# AVR_Board_4_0_FTDI_Ports.net
KiCad netlist of a schematic drawn in Altium Designer
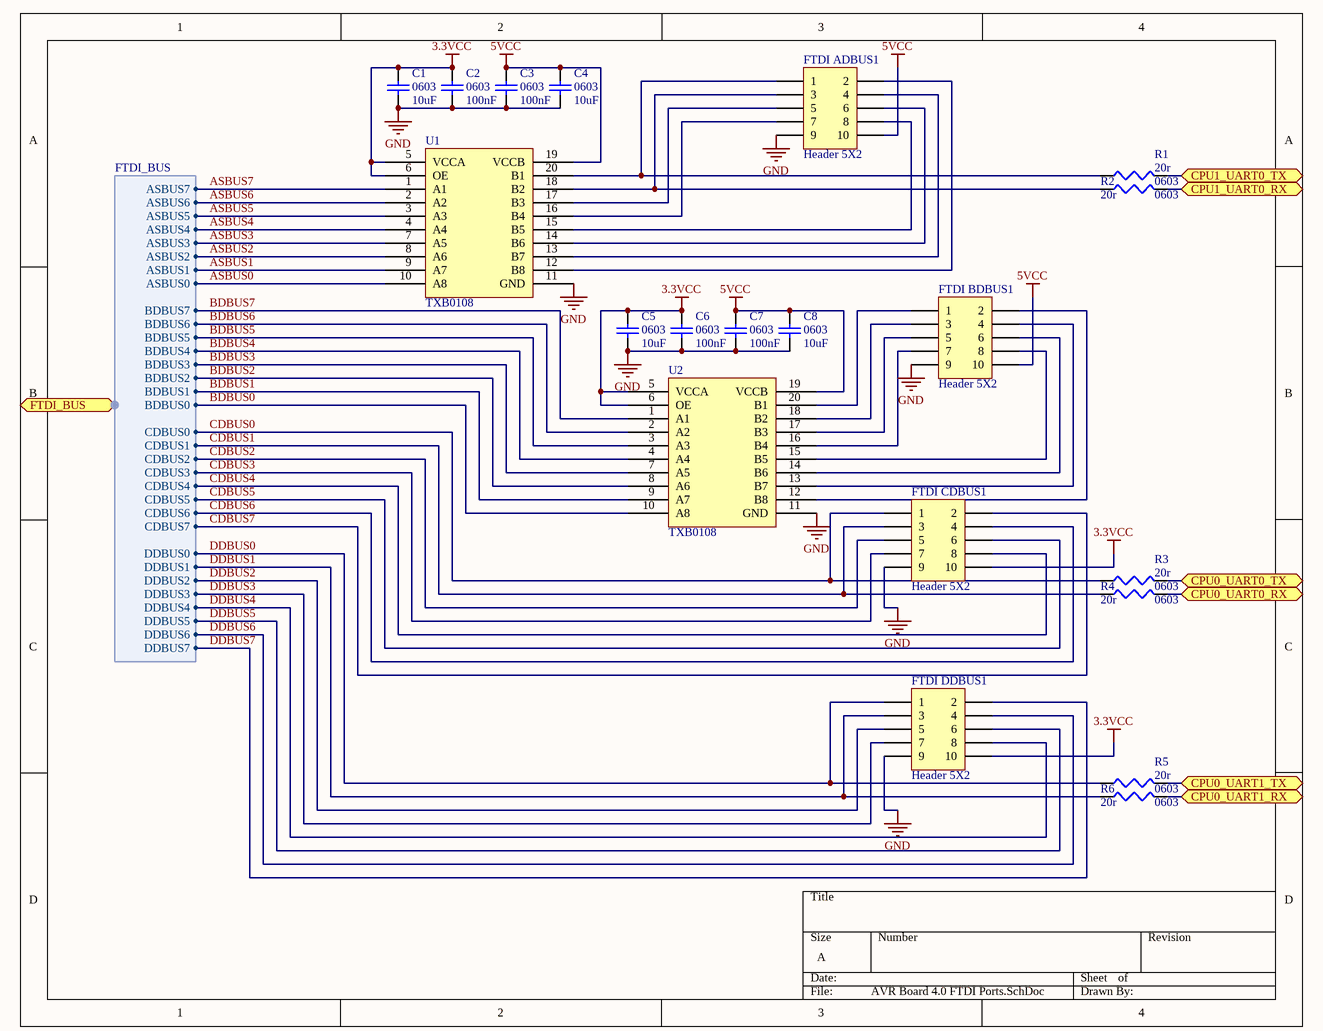
[diagram p0: AVR Board 4.0 FTDI Ports.SchDoc]

(export (version "E")
  (design (tool "Eeschema 10.0.6"))
  (components
    (comp (ref "C1")
      (value "0603")
      (footprint "1608[0603]")
      (description "Capacitor (Semiconductor SIM Model)")
      (fields (field (name "ALTIUM_VALUE") "10uF") (field (name "PUBLISHER") "Altium Limited"))
      (libsource (lib "Miscellaneous Devices") (part "Cap Semi"))
    )
    (comp (ref "C2")
      (value "0603")
      (footprint "1608[0603]")
      (description "Capacitor (Semiconductor SIM Model)")
      (fields (field (name "ALTIUM_VALUE") "100nF") (field (name "PUBLISHER") "Altium Limited"))
      (libsource (lib "Miscellaneous Devices") (part "Cap Semi"))
    )
    (comp (ref "C3")
      (value "0603")
      (footprint "1608[0603]")
      (description "Capacitor (Semiconductor SIM Model)")
      (fields (field (name "ALTIUM_VALUE") "100nF") (field (name "PUBLISHER") "Altium Limited"))
      (libsource (lib "Miscellaneous Devices") (part "Cap Semi"))
    )
    (comp (ref "C4")
      (value "0603")
      (footprint "1608[0603]")
      (description "Capacitor (Semiconductor SIM Model)")
      (fields (field (name "ALTIUM_VALUE") "10uF") (field (name "PUBLISHER") "Altium Limited"))
      (libsource (lib "Miscellaneous Devices") (part "Cap Semi"))
    )
    (comp (ref "C5")
      (value "0603")
      (footprint "1608[0603]")
      (description "Capacitor (Semiconductor SIM Model)")
      (fields (field (name "ALTIUM_VALUE") "10uF") (field (name "PUBLISHER") "Altium Limited"))
      (libsource (lib "Miscellaneous Devices") (part "Cap Semi"))
    )
    (comp (ref "C6")
      (value "0603")
      (footprint "1608[0603]")
      (description "Capacitor (Semiconductor SIM Model)")
      (fields (field (name "ALTIUM_VALUE") "100nF") (field (name "PUBLISHER") "Altium Limited"))
      (libsource (lib "Miscellaneous Devices") (part "Cap Semi"))
    )
    (comp (ref "C7")
      (value "0603")
      (footprint "1608[0603]")
      (description "Capacitor (Semiconductor SIM Model)")
      (fields (field (name "ALTIUM_VALUE") "100nF") (field (name "PUBLISHER") "Altium Limited"))
      (libsource (lib "Miscellaneous Devices") (part "Cap Semi"))
    )
    (comp (ref "C8")
      (value "0603")
      (footprint "1608[0603]")
      (description "Capacitor (Semiconductor SIM Model)")
      (fields (field (name "ALTIUM_VALUE") "10uF") (field (name "PUBLISHER") "Altium Limited"))
      (libsource (lib "Miscellaneous Devices") (part "Cap Semi"))
    )
    (comp (ref "FTDI ADBUS1")
      (value "Header 5X2")
      (footprint "HDR2X5")
      (description "Header, 5-Pin, Dual row")
      (fields (field (name "PUBLISHER") "Altium Limited"))
      (libsource (lib "Miscellaneous Connectors") (part "Header 5X2"))
    )
    (comp (ref "FTDI BDBUS1")
      (value "Header 5X2")
      (footprint "HDR2X5")
      (description "Header, 5-Pin, Dual row")
      (fields (field (name "PUBLISHER") "Altium Limited"))
      (libsource (lib "Miscellaneous Connectors") (part "Header 5X2"))
    )
    (comp (ref "FTDI CDBUS1")
      (value "Header 5X2")
      (footprint "HDR2X5")
      (description "Header, 5-Pin, Dual row")
      (fields (field (name "PUBLISHER") "Altium Limited"))
      (libsource (lib "Miscellaneous Connectors") (part "Header 5X2"))
    )
    (comp (ref "FTDI DDBUS1")
      (value "Header 5X2")
      (footprint "HDR2X5")
      (description "Header, 5-Pin, Dual row")
      (fields (field (name "PUBLISHER") "Altium Limited"))
      (libsource (lib "Miscellaneous Connectors") (part "Header 5X2"))
    )
    (comp (ref "R1")
      (value "0603")
      (footprint "J1-0603")
      (description "Resistor")
      (fields (field (name "ALTIUM_VALUE") "20r") (field (name "PUBLISHER") "Altium Limited"))
      (libsource (lib "Miscellaneous Devices") (part "Res3"))
    )
    (comp (ref "R2")
      (value "0603")
      (footprint "J1-0603")
      (description "Resistor")
      (fields (field (name "ALTIUM_VALUE") "20r") (field (name "PUBLISHER") "Altium Limited"))
      (libsource (lib "Miscellaneous Devices") (part "Res3"))
    )
    (comp (ref "R3")
      (value "0603")
      (footprint "J1-0603")
      (description "Resistor")
      (fields (field (name "ALTIUM_VALUE") "20r") (field (name "PUBLISHER") "Altium Limited"))
      (libsource (lib "Miscellaneous Devices") (part "Res3"))
    )
    (comp (ref "R4")
      (value "0603")
      (footprint "J1-0603")
      (description "Resistor")
      (fields (field (name "ALTIUM_VALUE") "20r") (field (name "PUBLISHER") "Altium Limited"))
      (libsource (lib "Miscellaneous Devices") (part "Res3"))
    )
    (comp (ref "R5")
      (value "0603")
      (footprint "J1-0603")
      (description "Resistor")
      (fields (field (name "ALTIUM_VALUE") "20r") (field (name "PUBLISHER") "Altium Limited"))
      (libsource (lib "Miscellaneous Devices") (part "Res3"))
    )
    (comp (ref "R6")
      (value "0603")
      (footprint "J1-0603")
      (description "Resistor")
      (fields (field (name "ALTIUM_VALUE") "20r") (field (name "PUBLISHER") "Altium Limited"))
      (libsource (lib "Miscellaneous Devices") (part "Res3"))
    )
    (comp (ref "U1")
      (value "TXB0108")
      (footprint "TXB0108")
      (description "Ti TXB0108 Bidirectional Level Translator")
      (libsource (lib "AVR Board 4.0 Symbol Lib") (part "TXB0108"))
    )
    (comp (ref "U2")
      (value "TXB0108")
      (footprint "TXB0108")
      (description "Ti TXB0108 Bidirectional Level Translator")
      (libsource (lib "AVR Board 4.0 Symbol Lib") (part "TXB0108"))
    )
  )
  (nets
    (net (code "2") (name "/ASBUS0") (class "Default")
      (node (ref "U1") (pin "10") (pinfunction "A8_10") (pintype "passive"))
    )
    (net (code "3") (name "/ASBUS1") (class "Default")
      (node (ref "U1") (pin "9") (pinfunction "A7_9") (pintype "passive"))
    )
    (net (code "4") (name "/ASBUS2") (class "Default")
      (node (ref "U1") (pin "8") (pinfunction "A6_8") (pintype "passive"))
    )
    (net (code "5") (name "/ASBUS3") (class "Default")
      (node (ref "U1") (pin "7") (pinfunction "A5_7") (pintype "passive"))
    )
    (net (code "6") (name "/ASBUS4") (class "Default")
      (node (ref "U1") (pin "4") (pinfunction "A4_4") (pintype "passive"))
    )
    (net (code "7") (name "/ASBUS5") (class "Default")
      (node (ref "U1") (pin "3") (pinfunction "A3_3") (pintype "passive"))
    )
    (net (code "8") (name "/ASBUS6") (class "Default")
      (node (ref "U1") (pin "2") (pinfunction "A2_2") (pintype "passive"))
    )
    (net (code "9") (name "/ASBUS7") (class "Default")
      (node (ref "U1") (pin "1") (pinfunction "A1_1") (pintype "passive"))
    )
    (net (code "10") (name "/BDBUS0") (class "Default")
      (node (ref "U2") (pin "10") (pinfunction "A8_10") (pintype "passive"))
    )
    (net (code "11") (name "/BDBUS1") (class "Default")
      (node (ref "U2") (pin "9") (pinfunction "A7_9") (pintype "passive"))
    )
    (net (code "12") (name "/BDBUS2") (class "Default")
      (node (ref "U2") (pin "8") (pinfunction "A6_8") (pintype "passive"))
    )
    (net (code "13") (name "/BDBUS3") (class "Default")
      (node (ref "U2") (pin "7") (pinfunction "A5_7") (pintype "passive"))
    )
    (net (code "14") (name "/BDBUS4") (class "Default")
      (node (ref "U2") (pin "4") (pinfunction "A4_4") (pintype "passive"))
    )
    (net (code "15") (name "/BDBUS5") (class "Default")
      (node (ref "U2") (pin "3") (pinfunction "A3_3") (pintype "passive"))
    )
    (net (code "16") (name "/BDBUS6") (class "Default")
      (node (ref "U2") (pin "2") (pinfunction "A2_2") (pintype "passive"))
    )
    (net (code "17") (name "/BDBUS7") (class "Default")
      (node (ref "U2") (pin "1") (pinfunction "A1_1") (pintype "passive"))
    )
    (net (code "18") (name "/CDBUS0") (class "Default")
      (node (ref "FTDI CDBUS1") (pin "1") (pinfunction "1_1") (pintype "passive"))
      (node (ref "R3") (pin "1") (pinfunction "1_1") (pintype "passive"))
    )
    (net (code "19") (name "/CDBUS1") (class "Default")
      (node (ref "FTDI CDBUS1") (pin "3") (pinfunction "3_3") (pintype "passive"))
      (node (ref "R4") (pin "1") (pinfunction "1_1") (pintype "passive"))
    )
    (net (code "20") (name "/CDBUS2") (class "Default")
      (node (ref "FTDI CDBUS1") (pin "5") (pinfunction "5_5") (pintype "passive"))
    )
    (net (code "21") (name "/CDBUS3") (class "Default")
      (node (ref "FTDI CDBUS1") (pin "7") (pinfunction "7_7") (pintype "passive"))
    )
    (net (code "22") (name "/CDBUS4") (class "Default")
      (node (ref "FTDI CDBUS1") (pin "8") (pinfunction "8_8") (pintype "passive"))
    )
    (net (code "23") (name "/CDBUS5") (class "Default")
      (node (ref "FTDI CDBUS1") (pin "6") (pinfunction "6_6") (pintype "passive"))
    )
    (net (code "24") (name "/CDBUS6") (class "Default")
      (node (ref "FTDI CDBUS1") (pin "4") (pinfunction "4_4") (pintype "passive"))
    )
    (net (code "25") (name "/CDBUS7") (class "Default")
      (node (ref "FTDI CDBUS1") (pin "2") (pinfunction "2_2") (pintype "passive"))
    )
    (net (code "26") (name "/CPU0_UART0_RX") (class "Default")
      (node (ref "R4") (pin "2") (pinfunction "2_2") (pintype "passive"))
    )
    (net (code "27") (name "/CPU0_UART0_TX") (class "Default")
      (node (ref "R3") (pin "2") (pinfunction "2_2") (pintype "passive"))
    )
    (net (code "28") (name "/CPU0_UART1_RX") (class "Default")
      (node (ref "R6") (pin "2") (pinfunction "2_2") (pintype "passive"))
    )
    (net (code "29") (name "/CPU0_UART1_TX") (class "Default")
      (node (ref "R5") (pin "2") (pinfunction "2_2") (pintype "passive"))
    )
    (net (code "30") (name "/CPU1_UART0_RX") (class "Default")
      (node (ref "R2") (pin "2") (pinfunction "2_2") (pintype "passive"))
    )
    (net (code "31") (name "/CPU1_UART0_TX") (class "Default")
      (node (ref "R1") (pin "2") (pinfunction "2_2") (pintype "passive"))
    )
    (net (code "32") (name "/DDBUS0") (class "Default")
      (node (ref "FTDI DDBUS1") (pin "1") (pinfunction "1_1") (pintype "passive"))
      (node (ref "R5") (pin "1") (pinfunction "1_1") (pintype "passive"))
    )
    (net (code "33") (name "/DDBUS1") (class "Default")
      (node (ref "FTDI DDBUS1") (pin "3") (pinfunction "3_3") (pintype "passive"))
      (node (ref "R6") (pin "1") (pinfunction "1_1") (pintype "passive"))
    )
    (net (code "34") (name "/DDBUS2") (class "Default")
      (node (ref "FTDI DDBUS1") (pin "5") (pinfunction "5_5") (pintype "passive"))
    )
    (net (code "35") (name "/DDBUS3") (class "Default")
      (node (ref "FTDI DDBUS1") (pin "7") (pinfunction "7_7") (pintype "passive"))
    )
    (net (code "36") (name "/DDBUS4") (class "Default")
      (node (ref "FTDI DDBUS1") (pin "8") (pinfunction "8_8") (pintype "passive"))
    )
    (net (code "37") (name "/DDBUS5") (class "Default")
      (node (ref "FTDI DDBUS1") (pin "6") (pinfunction "6_6") (pintype "passive"))
    )
    (net (code "38") (name "/DDBUS6") (class "Default")
      (node (ref "FTDI DDBUS1") (pin "4") (pinfunction "4_4") (pintype "passive"))
    )
    (net (code "39") (name "/DDBUS7") (class "Default")
      (node (ref "FTDI DDBUS1") (pin "2") (pinfunction "2_2") (pintype "passive"))
    )
    (net (code "41") (name "3.3VCC") (class "Default")
      (node (ref "C1") (pin "2") (pinfunction "2_2") (pintype "passive"))
      (node (ref "C2") (pin "2") (pinfunction "2_2") (pintype "passive"))
      (node (ref "C5") (pin "2") (pinfunction "2_2") (pintype "passive"))
      (node (ref "C6") (pin "2") (pinfunction "2_2") (pintype "passive"))
      (node (ref "FTDI CDBUS1") (pin "10") (pinfunction "10_10") (pintype "passive"))
      (node (ref "FTDI DDBUS1") (pin "10") (pinfunction "10_10") (pintype "passive"))
      (node (ref "U1") (pin "5") (pinfunction "VCCA_5") (pintype "passive"))
      (node (ref "U1") (pin "6") (pinfunction "OE_6") (pintype "passive"))
      (node (ref "U2") (pin "5") (pinfunction "VCCA_5") (pintype "passive"))
      (node (ref "U2") (pin "6") (pinfunction "OE_6") (pintype "passive"))
    )
    (net (code "42") (name "5VCC") (class "Default")
      (node (ref "C3") (pin "2") (pinfunction "2_2") (pintype "passive"))
      (node (ref "C4") (pin "2") (pinfunction "2_2") (pintype "passive"))
      (node (ref "C7") (pin "2") (pinfunction "2_2") (pintype "passive"))
      (node (ref "C8") (pin "2") (pinfunction "2_2") (pintype "passive"))
      (node (ref "FTDI ADBUS1") (pin "10") (pinfunction "10_10") (pintype "passive"))
      (node (ref "FTDI BDBUS1") (pin "10") (pinfunction "10_10") (pintype "passive"))
      (node (ref "U1") (pin "19") (pinfunction "VCCB_19") (pintype "passive"))
      (node (ref "U2") (pin "19") (pinfunction "VCCB_19") (pintype "passive"))
    )
    (net (code "43") (name "GND") (class "Default")
      (node (ref "C1") (pin "1") (pinfunction "1_1") (pintype "passive"))
      (node (ref "C2") (pin "1") (pinfunction "1_1") (pintype "passive"))
      (node (ref "C3") (pin "1") (pinfunction "1_1") (pintype "passive"))
      (node (ref "C4") (pin "1") (pinfunction "1_1") (pintype "passive"))
      (node (ref "C5") (pin "1") (pinfunction "1_1") (pintype "passive"))
      (node (ref "C6") (pin "1") (pinfunction "1_1") (pintype "passive"))
      (node (ref "C7") (pin "1") (pinfunction "1_1") (pintype "passive"))
      (node (ref "C8") (pin "1") (pinfunction "1_1") (pintype "passive"))
      (node (ref "FTDI ADBUS1") (pin "9") (pinfunction "9_9") (pintype "passive"))
      (node (ref "FTDI BDBUS1") (pin "9") (pinfunction "9_9") (pintype "passive"))
      (node (ref "FTDI CDBUS1") (pin "9") (pinfunction "9_9") (pintype "passive"))
      (node (ref "FTDI DDBUS1") (pin "9") (pinfunction "9_9") (pintype "passive"))
      (node (ref "U1") (pin "11") (pinfunction "GND_11") (pintype "passive"))
      (node (ref "U2") (pin "11") (pinfunction "GND_11") (pintype "passive"))
    )
    (net (code "44") (name "Net-(U1-B1)") (class "Default")
      (node (ref "FTDI ADBUS1") (pin "1") (pinfunction "1_1") (pintype "passive"))
      (node (ref "R1") (pin "1") (pinfunction "1_1") (pintype "passive"))
      (node (ref "U1") (pin "20") (pinfunction "B1_20") (pintype "passive"))
    )
    (net (code "45") (name "Net-(U1-B2)") (class "Default")
      (node (ref "FTDI ADBUS1") (pin "3") (pinfunction "3_3") (pintype "passive"))
      (node (ref "R2") (pin "1") (pinfunction "1_1") (pintype "passive"))
      (node (ref "U1") (pin "18") (pinfunction "B2_18") (pintype "passive"))
    )
    (net (code "46") (name "Net-(U1-B3)") (class "Default")
      (node (ref "FTDI ADBUS1") (pin "5") (pinfunction "5_5") (pintype "passive"))
      (node (ref "U1") (pin "17") (pinfunction "B3_17") (pintype "passive"))
    )
    (net (code "47") (name "Net-(U1-B4)") (class "Default")
      (node (ref "FTDI ADBUS1") (pin "7") (pinfunction "7_7") (pintype "passive"))
      (node (ref "U1") (pin "16") (pinfunction "B4_16") (pintype "passive"))
    )
    (net (code "48") (name "Net-(U1-B5)") (class "Default")
      (node (ref "FTDI ADBUS1") (pin "8") (pinfunction "8_8") (pintype "passive"))
      (node (ref "U1") (pin "15") (pinfunction "B5_15") (pintype "passive"))
    )
    (net (code "49") (name "Net-(U1-B6)") (class "Default")
      (node (ref "FTDI ADBUS1") (pin "6") (pinfunction "6_6") (pintype "passive"))
      (node (ref "U1") (pin "14") (pinfunction "B6_14") (pintype "passive"))
    )
    (net (code "50") (name "Net-(U1-B7)") (class "Default")
      (node (ref "FTDI ADBUS1") (pin "4") (pinfunction "4_4") (pintype "passive"))
      (node (ref "U1") (pin "13") (pinfunction "B7_13") (pintype "passive"))
    )
    (net (code "51") (name "Net-(U1-B8)") (class "Default")
      (node (ref "FTDI ADBUS1") (pin "2") (pinfunction "2_2") (pintype "passive"))
      (node (ref "U1") (pin "12") (pinfunction "B8_12") (pintype "passive"))
    )
    (net (code "52") (name "Net-(U2-B1)") (class "Default")
      (node (ref "FTDI BDBUS1") (pin "1") (pinfunction "1_1") (pintype "passive"))
      (node (ref "U2") (pin "20") (pinfunction "B1_20") (pintype "passive"))
    )
    (net (code "53") (name "Net-(U2-B2)") (class "Default")
      (node (ref "FTDI BDBUS1") (pin "3") (pinfunction "3_3") (pintype "passive"))
      (node (ref "U2") (pin "18") (pinfunction "B2_18") (pintype "passive"))
    )
    (net (code "54") (name "Net-(U2-B3)") (class "Default")
      (node (ref "FTDI BDBUS1") (pin "5") (pinfunction "5_5") (pintype "passive"))
      (node (ref "U2") (pin "17") (pinfunction "B3_17") (pintype "passive"))
    )
    (net (code "55") (name "Net-(U2-B4)") (class "Default")
      (node (ref "FTDI BDBUS1") (pin "7") (pinfunction "7_7") (pintype "passive"))
      (node (ref "U2") (pin "16") (pinfunction "B4_16") (pintype "passive"))
    )
    (net (code "56") (name "Net-(U2-B5)") (class "Default")
      (node (ref "FTDI BDBUS1") (pin "8") (pinfunction "8_8") (pintype "passive"))
      (node (ref "U2") (pin "15") (pinfunction "B5_15") (pintype "passive"))
    )
    (net (code "57") (name "Net-(U2-B6)") (class "Default")
      (node (ref "FTDI BDBUS1") (pin "6") (pinfunction "6_6") (pintype "passive"))
      (node (ref "U2") (pin "14") (pinfunction "B6_14") (pintype "passive"))
    )
    (net (code "58") (name "Net-(U2-B7)") (class "Default")
      (node (ref "FTDI BDBUS1") (pin "4") (pinfunction "4_4") (pintype "passive"))
      (node (ref "U2") (pin "13") (pinfunction "B7_13") (pintype "passive"))
    )
    (net (code "59") (name "Net-(U2-B8)") (class "Default")
      (node (ref "FTDI BDBUS1") (pin "2") (pinfunction "2_2") (pintype "passive"))
      (node (ref "U2") (pin "12") (pinfunction "B8_12") (pintype "passive"))
    )
  )
)
